# 4-PT100.net
KiCad netlist of a schematic drawn in EAGLE
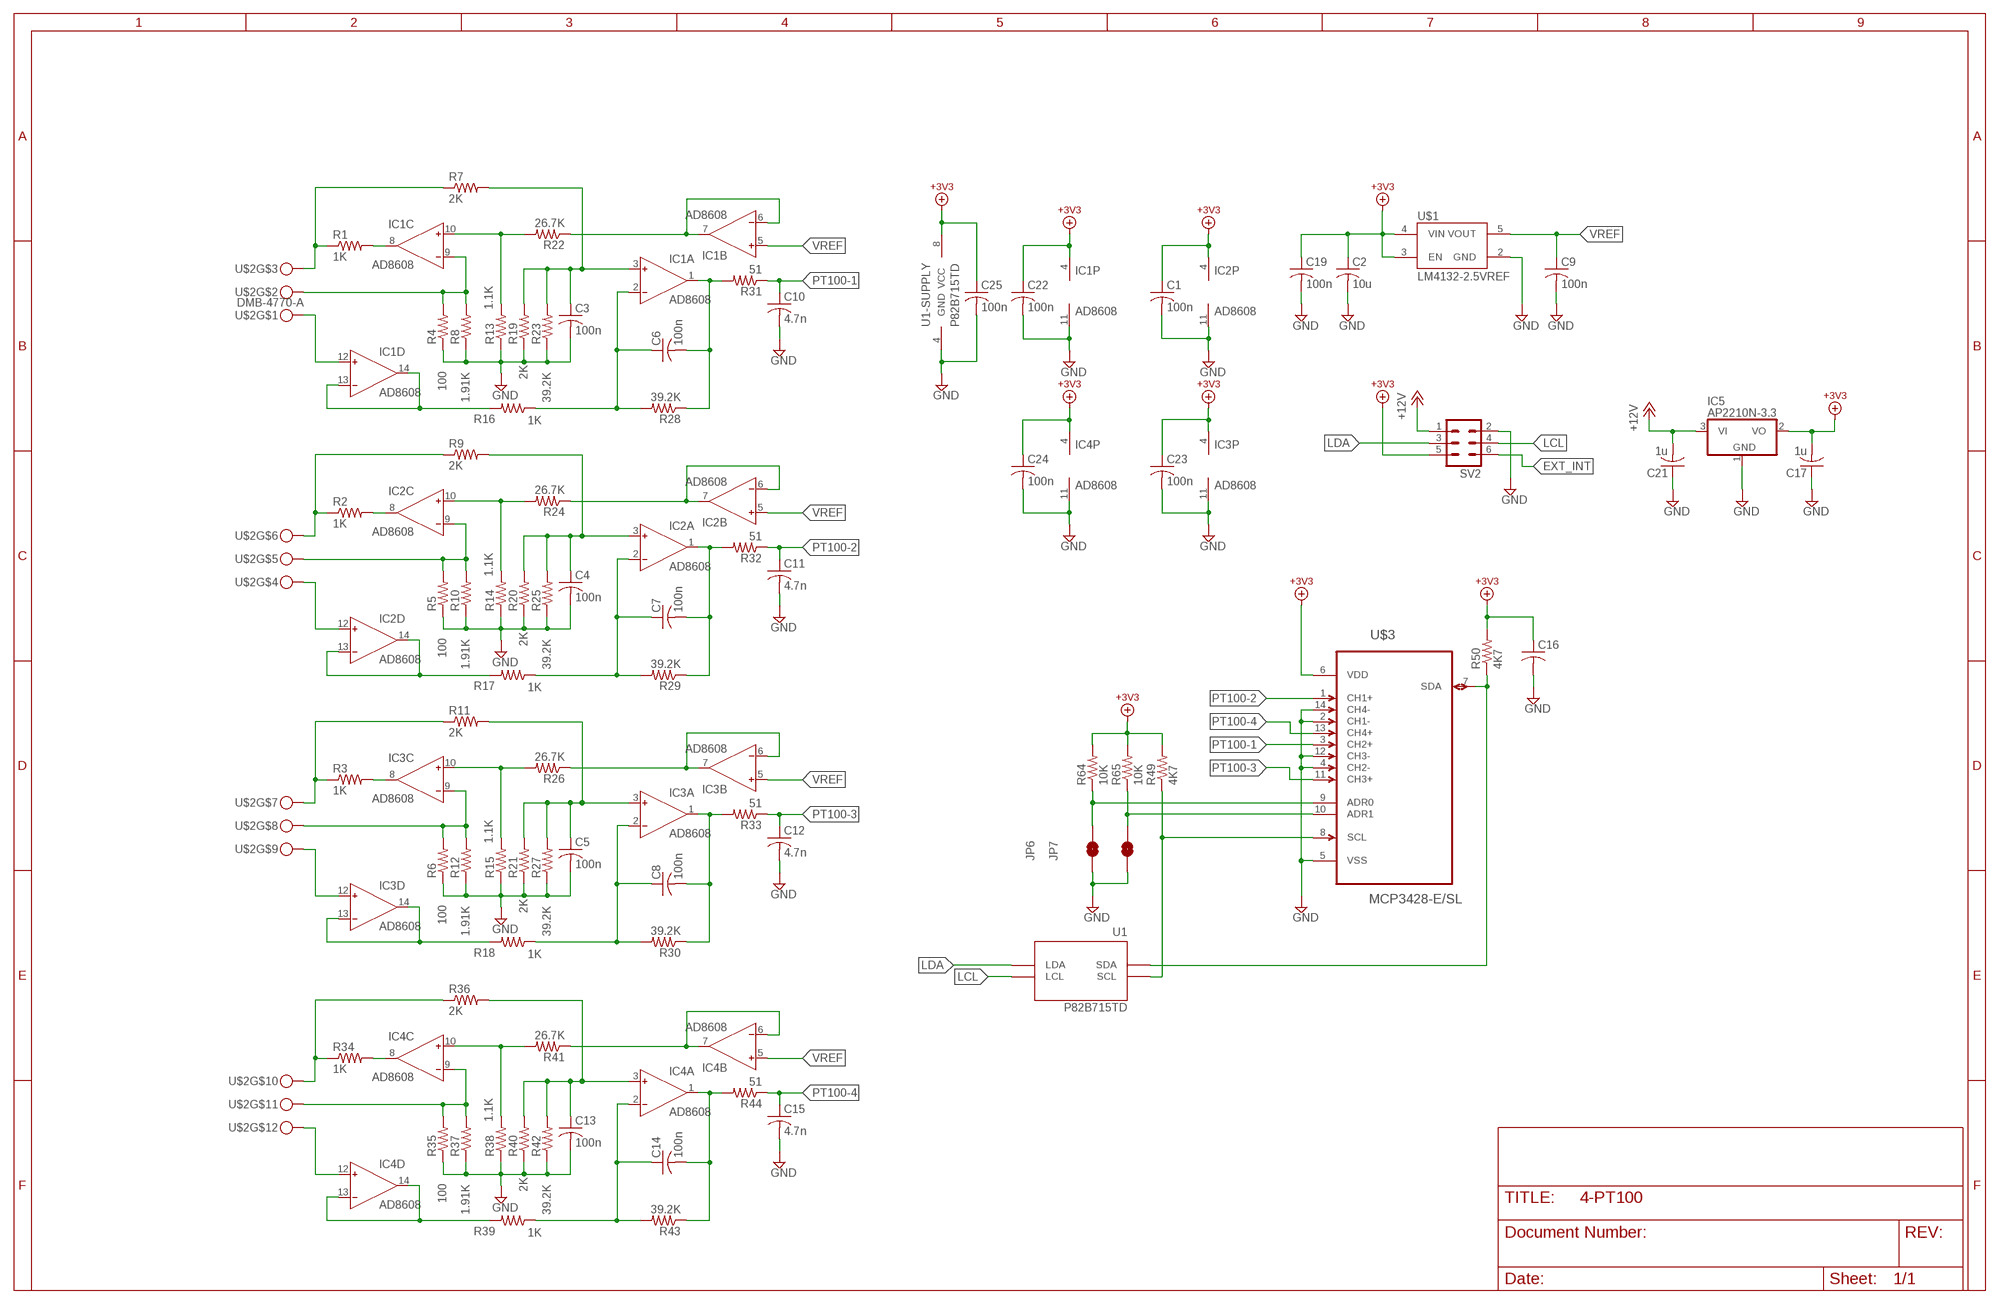
[diagram p0: schematic, sheet 1]

(export (version "E")
  (design (tool "Eeschema 10.0.6"))
  (components
    (comp (ref "C1")
      (value "100n")
      (footprint "eagle-import:C0805")
      (libsource (lib "eagle-import") (part "C-USC0805"))
    )
    (comp (ref "C2")
      (value "10u")
      (footprint "eagle-import:C0805")
      (libsource (lib "eagle-import") (part "C-USC0805"))
    )
    (comp (ref "C3")
      (value "100n")
      (footprint "eagle-import:C0805")
      (libsource (lib "eagle-import") (part "C-USC0805"))
    )
    (comp (ref "C4")
      (value "100n")
      (footprint "eagle-import:C0805")
      (libsource (lib "eagle-import") (part "C-USC0805"))
    )
    (comp (ref "C5")
      (value "100n")
      (footprint "eagle-import:C0805")
      (libsource (lib "eagle-import") (part "C-USC0805"))
    )
    (comp (ref "C6")
      (value "100n")
      (footprint "eagle-import:C0805")
      (libsource (lib "eagle-import") (part "C-USC0805"))
    )
    (comp (ref "C7")
      (value "100n")
      (footprint "eagle-import:C0805")
      (libsource (lib "eagle-import") (part "C-USC0805"))
    )
    (comp (ref "C8")
      (value "100n")
      (footprint "eagle-import:C0805")
      (libsource (lib "eagle-import") (part "C-USC0805"))
    )
    (comp (ref "C9")
      (value "100n")
      (footprint "eagle-import:C0805")
      (libsource (lib "eagle-import") (part "C-USC0805"))
    )
    (comp (ref "C10")
      (value "4.7n")
      (footprint "eagle-import:C0805")
      (libsource (lib "eagle-import") (part "C-USC0805"))
    )
    (comp (ref "C11")
      (value "4.7n")
      (footprint "eagle-import:C0805")
      (libsource (lib "eagle-import") (part "C-USC0805"))
    )
    (comp (ref "C12")
      (value "4.7n")
      (footprint "eagle-import:C0805")
      (libsource (lib "eagle-import") (part "C-USC0805"))
    )
    (comp (ref "C13")
      (value "100n")
      (footprint "eagle-import:C0805")
      (libsource (lib "eagle-import") (part "C-USC0805"))
    )
    (comp (ref "C14")
      (value "100n")
      (footprint "eagle-import:C0805")
      (libsource (lib "eagle-import") (part "C-USC0805"))
    )
    (comp (ref "C15")
      (value "4.7n")
      (footprint "eagle-import:C0805")
      (libsource (lib "eagle-import") (part "C-USC0805"))
    )
    (comp (ref "C16")
      (value "C-USC0805")
      (footprint "eagle-import:C0805")
      (libsource (lib "eagle-import") (part "C-USC0805"))
    )
    (comp (ref "C17")
      (value "1u")
      (footprint "eagle-import:C0805")
      (libsource (lib "eagle-import") (part "C-USC0805"))
    )
    (comp (ref "C19")
      (value "100n")
      (footprint "eagle-import:C0805")
      (libsource (lib "eagle-import") (part "C-USC0805"))
    )
    (comp (ref "C21")
      (value "1u")
      (footprint "eagle-import:C0805")
      (libsource (lib "eagle-import") (part "C-USC0805"))
    )
    (comp (ref "C22")
      (value "100n")
      (footprint "eagle-import:C0805")
      (libsource (lib "eagle-import") (part "C-USC0805"))
    )
    (comp (ref "C23")
      (value "100n")
      (footprint "eagle-import:C0805")
      (libsource (lib "eagle-import") (part "C-USC0805"))
    )
    (comp (ref "C24")
      (value "100n")
      (footprint "eagle-import:C0805")
      (libsource (lib "eagle-import") (part "C-USC0805"))
    )
    (comp (ref "C25")
      (value "100n")
      (footprint "eagle-import:C0805")
      (libsource (lib "eagle-import") (part "C-USC0805"))
    )
    (comp (ref "IC1")
      (value "AD8608")
      (footprint "eagle-import:SO14")
      (fields (field (name "MPN") "AD8609ARZ"))
      (libsource (lib "eagle-import") (part "AD8609R"))
    )
    (comp (ref "IC2")
      (value "AD8608")
      (footprint "eagle-import:SO14")
      (fields (field (name "MPN") "AD8609ARZ"))
      (libsource (lib "eagle-import") (part "AD8609R"))
    )
    (comp (ref "IC3")
      (value "AD8608")
      (footprint "eagle-import:SO14")
      (fields (field (name "MPN") "AD8609ARZ"))
      (libsource (lib "eagle-import") (part "AD8609R"))
    )
    (comp (ref "IC4")
      (value "AD8608")
      (footprint "eagle-import:SO14")
      (fields (field (name "MPN") "AD8609ARZ"))
      (libsource (lib "eagle-import") (part "AD8609R"))
    )
    (comp (ref "IC5")
      (value "AP2210N-3.3")
      (footprint "eagle-import:SOT23")
      (libsource (lib "eagle-import") (part "MCP1703CB"))
    )
    (comp (ref "JP6")
      (value "JUMPER-PAD-2-NOYES_SILK")
      (footprint "eagle-import:PAD-JUMPER-2-NO_YES_SILK")
      (libsource (lib "eagle-import") (part "JUMPER-PAD-2-NOYES_SILK"))
    )
    (comp (ref "JP7")
      (value "JUMPER-PAD-2-NOYES_SILK")
      (footprint "eagle-import:PAD-JUMPER-2-NO_YES_SILK")
      (libsource (lib "eagle-import") (part "JUMPER-PAD-2-NOYES_SILK"))
    )
    (comp (ref "R1")
      (value "1K")
      (footprint "eagle-import:R0805")
      (libsource (lib "eagle-import") (part "R-US_R0805"))
    )
    (comp (ref "R2")
      (value "1K")
      (footprint "eagle-import:R0805")
      (libsource (lib "eagle-import") (part "R-US_R0805"))
    )
    (comp (ref "R3")
      (value "1K")
      (footprint "eagle-import:R0805")
      (libsource (lib "eagle-import") (part "R-US_R0805"))
    )
    (comp (ref "R4")
      (value "100")
      (footprint "eagle-import:R0805")
      (libsource (lib "eagle-import") (part "R-US_R0805"))
    )
    (comp (ref "R5")
      (value "100")
      (footprint "eagle-import:R0805")
      (libsource (lib "eagle-import") (part "R-US_R0805"))
    )
    (comp (ref "R6")
      (value "100")
      (footprint "eagle-import:R0805")
      (libsource (lib "eagle-import") (part "R-US_R0805"))
    )
    (comp (ref "R7")
      (value "2K")
      (footprint "eagle-import:R0805")
      (libsource (lib "eagle-import") (part "R-US_R0805"))
    )
    (comp (ref "R8")
      (value "1.91K")
      (footprint "eagle-import:R0805")
      (libsource (lib "eagle-import") (part "R-US_R0805"))
    )
    (comp (ref "R9")
      (value "2K")
      (footprint "eagle-import:R0805")
      (libsource (lib "eagle-import") (part "R-US_R0805"))
    )
    (comp (ref "R10")
      (value "1.91K")
      (footprint "eagle-import:R0805")
      (libsource (lib "eagle-import") (part "R-US_R0805"))
    )
    (comp (ref "R11")
      (value "2K")
      (footprint "eagle-import:R0805")
      (libsource (lib "eagle-import") (part "R-US_R0805"))
    )
    (comp (ref "R12")
      (value "1.91K")
      (footprint "eagle-import:R0805")
      (libsource (lib "eagle-import") (part "R-US_R0805"))
    )
    (comp (ref "R13")
      (value "1.1K")
      (footprint "eagle-import:R0805")
      (libsource (lib "eagle-import") (part "R-US_R0805"))
    )
    (comp (ref "R14")
      (value "1.1K")
      (footprint "eagle-import:R0805")
      (libsource (lib "eagle-import") (part "R-US_R0805"))
    )
    (comp (ref "R15")
      (value "1.1K")
      (footprint "eagle-import:R0805")
      (libsource (lib "eagle-import") (part "R-US_R0805"))
    )
    (comp (ref "R16")
      (value "1K")
      (footprint "eagle-import:R0805")
      (libsource (lib "eagle-import") (part "R-US_R0805"))
    )
    (comp (ref "R17")
      (value "1K")
      (footprint "eagle-import:R0805")
      (libsource (lib "eagle-import") (part "R-US_R0805"))
    )
    (comp (ref "R18")
      (value "1K")
      (footprint "eagle-import:R0805")
      (libsource (lib "eagle-import") (part "R-US_R0805"))
    )
    (comp (ref "R19")
      (value "2K")
      (footprint "eagle-import:R0805")
      (libsource (lib "eagle-import") (part "R-US_R0805"))
    )
    (comp (ref "R20")
      (value "2K")
      (footprint "eagle-import:R0805")
      (libsource (lib "eagle-import") (part "R-US_R0805"))
    )
    (comp (ref "R21")
      (value "2K")
      (footprint "eagle-import:R0805")
      (libsource (lib "eagle-import") (part "R-US_R0805"))
    )
    (comp (ref "R22")
      (value "26.7K")
      (footprint "eagle-import:R0805")
      (libsource (lib "eagle-import") (part "R-US_R0805"))
    )
    (comp (ref "R23")
      (value "39.2K")
      (footprint "eagle-import:R0805")
      (libsource (lib "eagle-import") (part "R-US_R0805"))
    )
    (comp (ref "R24")
      (value "26.7K")
      (footprint "eagle-import:R0805")
      (libsource (lib "eagle-import") (part "R-US_R0805"))
    )
    (comp (ref "R25")
      (value "39.2K")
      (footprint "eagle-import:R0805")
      (libsource (lib "eagle-import") (part "R-US_R0805"))
    )
    (comp (ref "R26")
      (value "26.7K")
      (footprint "eagle-import:R0805")
      (libsource (lib "eagle-import") (part "R-US_R0805"))
    )
    (comp (ref "R27")
      (value "39.2K")
      (footprint "eagle-import:R0805")
      (libsource (lib "eagle-import") (part "R-US_R0805"))
    )
    (comp (ref "R28")
      (value "39.2K")
      (footprint "eagle-import:R0805")
      (libsource (lib "eagle-import") (part "R-US_R0805"))
    )
    (comp (ref "R29")
      (value "39.2K")
      (footprint "eagle-import:R0805")
      (libsource (lib "eagle-import") (part "R-US_R0805"))
    )
    (comp (ref "R30")
      (value "39.2K")
      (footprint "eagle-import:R0805")
      (libsource (lib "eagle-import") (part "R-US_R0805"))
    )
    (comp (ref "R31")
      (value "51")
      (footprint "eagle-import:R0805")
      (libsource (lib "eagle-import") (part "R-US_R0805"))
    )
    (comp (ref "R32")
      (value "51")
      (footprint "eagle-import:R0805")
      (libsource (lib "eagle-import") (part "R-US_R0805"))
    )
    (comp (ref "R33")
      (value "51")
      (footprint "eagle-import:R0805")
      (libsource (lib "eagle-import") (part "R-US_R0805"))
    )
    (comp (ref "R34")
      (value "1K")
      (footprint "eagle-import:R0805")
      (libsource (lib "eagle-import") (part "R-US_R0805"))
    )
    (comp (ref "R35")
      (value "100")
      (footprint "eagle-import:R0805")
      (libsource (lib "eagle-import") (part "R-US_R0805"))
    )
    (comp (ref "R36")
      (value "2K")
      (footprint "eagle-import:R0805")
      (libsource (lib "eagle-import") (part "R-US_R0805"))
    )
    (comp (ref "R37")
      (value "1.91K")
      (footprint "eagle-import:R0805")
      (libsource (lib "eagle-import") (part "R-US_R0805"))
    )
    (comp (ref "R38")
      (value "1.1K")
      (footprint "eagle-import:R0805")
      (libsource (lib "eagle-import") (part "R-US_R0805"))
    )
    (comp (ref "R39")
      (value "1K")
      (footprint "eagle-import:R0805")
      (libsource (lib "eagle-import") (part "R-US_R0805"))
    )
    (comp (ref "R40")
      (value "2K")
      (footprint "eagle-import:R0805")
      (libsource (lib "eagle-import") (part "R-US_R0805"))
    )
    (comp (ref "R41")
      (value "26.7K")
      (footprint "eagle-import:R0805")
      (libsource (lib "eagle-import") (part "R-US_R0805"))
    )
    (comp (ref "R42")
      (value "39.2K")
      (footprint "eagle-import:R0805")
      (libsource (lib "eagle-import") (part "R-US_R0805"))
    )
    (comp (ref "R43")
      (value "39.2K")
      (footprint "eagle-import:R0805")
      (libsource (lib "eagle-import") (part "R-US_R0805"))
    )
    (comp (ref "R44")
      (value "51")
      (footprint "eagle-import:R0805")
      (libsource (lib "eagle-import") (part "R-US_R0805"))
    )
    (comp (ref "R49")
      (value "4K7")
      (footprint "eagle-import:R0805")
      (libsource (lib "eagle-import") (part "R-US_R0805"))
    )
    (comp (ref "R50")
      (value "4K7")
      (footprint "eagle-import:R0805")
      (libsource (lib "eagle-import") (part "R-US_R0805"))
    )
    (comp (ref "R64")
      (value "10K")
      (footprint "eagle-import:R0805")
      (libsource (lib "eagle-import") (part "R-US_R0805"))
    )
    (comp (ref "R65")
      (value "10K")
      (footprint "eagle-import:R0805")
      (libsource (lib "eagle-import") (part "R-US_R0805"))
    )
    (comp (ref "SV2")
      (value "ML6")
      (footprint "eagle-import:ML6")
      (libsource (lib "eagle-import") (part "ML6"))
    )
    (comp (ref "U$1")
      (value "LM4132-2.5VREF")
      (footprint "eagle-import:SOT23-5")
      (libsource (lib "eagle-import") (part "LM4128-2.5VREF"))
    )
    (comp (ref "U$2")
      (value "DMB-4770-A")
      (footprint "eagle-import:DMB-4770-A-PKG")
      (libsource (lib "eagle-import") (part "DMB-4770-A"))
    )
    (comp (ref "U$3")
      (value "MCP3428-E/SL")
      (footprint "eagle-import:SOIC127P600X175-14N")
      (libsource (lib "eagle-import") (part "MCP3428-E/SL"))
    )
    (comp (ref "U1")
      (value "P82B715TD")
      (footprint "eagle-import:SOIC-8")
      (fields (field (name "MANUFACTURER") "NXP Semiconductors") (field (name "PART_NUMBER") "P82B715TD,118"))
      (libsource (lib "eagle-import") (part "P82B715?TD"))
    )
  )
  (nets
    (net (code "1") (name "+12V") (class "Default")
      (node (ref "C21") (pin "2") (pinfunction "2_2") (pintype "passive"))
      (node (ref "IC5") (pin "3") (pinfunction "VI_3") (pintype "input"))
      (node (ref "SV2") (pin "1") (pinfunction "1_1") (pintype "passive"))
    )
    (net (code "2") (name "EXT_INT") (class "Default")
      (node (ref "SV2") (pin "6") (pinfunction "6_6") (pintype "passive"))
    )
    (net (code "3") (name "GND") (class "Default")
      (node (ref "C1") (pin "2") (pinfunction "2_2") (pintype "passive"))
      (node (ref "C10") (pin "2") (pinfunction "2_2") (pintype "passive"))
      (node (ref "C11") (pin "2") (pinfunction "2_2") (pintype "passive"))
      (node (ref "C12") (pin "2") (pinfunction "2_2") (pintype "passive"))
      (node (ref "C13") (pin "2") (pinfunction "2_2") (pintype "passive"))
      (node (ref "C15") (pin "2") (pinfunction "2_2") (pintype "passive"))
      (node (ref "C16") (pin "2") (pinfunction "2_2") (pintype "passive"))
      (node (ref "C17") (pin "1") (pinfunction "1_1") (pintype "passive"))
      (node (ref "C19") (pin "2") (pinfunction "2_2") (pintype "passive"))
      (node (ref "C2") (pin "2") (pinfunction "2_2") (pintype "passive"))
      (node (ref "C21") (pin "1") (pinfunction "1_1") (pintype "passive"))
      (node (ref "C22") (pin "2") (pinfunction "2_2") (pintype "passive"))
      (node (ref "C23") (pin "2") (pinfunction "2_2") (pintype "passive"))
      (node (ref "C24") (pin "2") (pinfunction "2_2") (pintype "passive"))
      (node (ref "C25") (pin "2") (pinfunction "2_2") (pintype "passive"))
      (node (ref "C3") (pin "2") (pinfunction "2_2") (pintype "passive"))
      (node (ref "C4") (pin "2") (pinfunction "2_2") (pintype "passive"))
      (node (ref "C5") (pin "2") (pinfunction "2_2") (pintype "passive"))
      (node (ref "C9") (pin "2") (pinfunction "2_2") (pintype "passive"))
      (node (ref "IC1") (pin "11") (pinfunction "V-_11") (pintype "power_in"))
      (node (ref "IC2") (pin "11") (pinfunction "V-_11") (pintype "power_in"))
      (node (ref "IC3") (pin "11") (pinfunction "V-_11") (pintype "power_in"))
      (node (ref "IC4") (pin "11") (pinfunction "V-_11") (pintype "power_in"))
      (node (ref "IC5") (pin "1") (pinfunction "GND_1") (pintype "passive"))
      (node (ref "JP6") (pin "1") (pinfunction "1_1") (pintype "passive"))
      (node (ref "JP7") (pin "1") (pinfunction "1_1") (pintype "passive"))
      (node (ref "R10") (pin "1") (pinfunction "1_1") (pintype "passive"))
      (node (ref "R12") (pin "1") (pinfunction "1_1") (pintype "passive"))
      (node (ref "R13") (pin "1") (pinfunction "1_1") (pintype "passive"))
      (node (ref "R14") (pin "1") (pinfunction "1_1") (pintype "passive"))
      (node (ref "R15") (pin "1") (pinfunction "1_1") (pintype "passive"))
      (node (ref "R19") (pin "1") (pinfunction "1_1") (pintype "passive"))
      (node (ref "R20") (pin "1") (pinfunction "1_1") (pintype "passive"))
      (node (ref "R21") (pin "1") (pinfunction "1_1") (pintype "passive"))
      (node (ref "R23") (pin "1") (pinfunction "1_1") (pintype "passive"))
      (node (ref "R25") (pin "1") (pinfunction "1_1") (pintype "passive"))
      (node (ref "R27") (pin "1") (pinfunction "1_1") (pintype "passive"))
      (node (ref "R35") (pin "1") (pinfunction "1_1") (pintype "passive"))
      (node (ref "R37") (pin "1") (pinfunction "1_1") (pintype "passive"))
      (node (ref "R38") (pin "1") (pinfunction "1_1") (pintype "passive"))
      (node (ref "R4") (pin "1") (pinfunction "1_1") (pintype "passive"))
      (node (ref "R40") (pin "1") (pinfunction "1_1") (pintype "passive"))
      (node (ref "R42") (pin "1") (pinfunction "1_1") (pintype "passive"))
      (node (ref "R5") (pin "1") (pinfunction "1_1") (pintype "passive"))
      (node (ref "R6") (pin "1") (pinfunction "1_1") (pintype "passive"))
      (node (ref "R8") (pin "1") (pinfunction "1_1") (pintype "passive"))
      (node (ref "SV2") (pin "2") (pinfunction "2_2") (pintype "passive"))
      (node (ref "U$1") (pin "2") (pinfunction "GND_2") (pintype "bidirectional"))
      (node (ref "U$3") (pin "12") (pinfunction "CH3-_12") (pintype "input"))
      (node (ref "U$3") (pin "14") (pinfunction "CH4-_14") (pintype "input"))
      (node (ref "U$3") (pin "2") (pinfunction "CH1-_2") (pintype "input"))
      (node (ref "U$3") (pin "4") (pinfunction "CH2-_4") (pintype "input"))
      (node (ref "U$3") (pin "5") (pinfunction "VSS_5") (pintype "power_in"))
      (node (ref "U1") (pin "4") (pinfunction "GND_4") (pintype "bidirectional"))
    )
    (net (code "4") (name "LCL") (class "Default")
      (node (ref "SV2") (pin "4") (pinfunction "4_4") (pintype "passive"))
      (node (ref "U1") (pin "2") (pinfunction "LCL_2") (pintype "bidirectional"))
    )
    (net (code "5") (name "LDA") (class "Default")
      (node (ref "SV2") (pin "3") (pinfunction "3_3") (pintype "passive"))
      (node (ref "U1") (pin "7") (pinfunction "LDA_7") (pintype "bidirectional"))
    )
    (net (code "6") (name "Net-(IC1A-IN+)") (class "Default")
      (node (ref "C3") (pin "1") (pinfunction "1_1") (pintype "passive"))
      (node (ref "IC1") (pin "3") (pinfunction "IN+_3") (pintype "input"))
      (node (ref "R19") (pin "2") (pinfunction "2_2") (pintype "passive"))
      (node (ref "R23") (pin "2") (pinfunction "2_2") (pintype "passive"))
      (node (ref "R7") (pin "2") (pinfunction "2_2") (pintype "passive"))
    )
    (net (code "7") (name "Net-(IC1A-IN-)") (class "Default")
      (node (ref "C6") (pin "1") (pinfunction "1_1") (pintype "passive"))
      (node (ref "IC1") (pin "2") (pinfunction "IN-_2") (pintype "input"))
      (node (ref "R16") (pin "1") (pinfunction "1_1") (pintype "passive"))
      (node (ref "R28") (pin "2") (pinfunction "2_2") (pintype "passive"))
    )
    (net (code "8") (name "Net-(IC1A-OUT)") (class "Default")
      (node (ref "C6") (pin "2") (pinfunction "2_2") (pintype "passive"))
      (node (ref "IC1") (pin "1") (pinfunction "OUT_1") (pintype "output"))
      (node (ref "R28") (pin "1") (pinfunction "1_1") (pintype "passive"))
      (node (ref "R31") (pin "2") (pinfunction "2_2") (pintype "passive"))
    )
    (net (code "9") (name "Net-(IC1B-IN-)") (class "Default")
      (node (ref "IC1") (pin "6") (pinfunction "IN-_6") (pintype "input"))
      (node (ref "IC1") (pin "7") (pinfunction "OUT_7") (pintype "output"))
      (node (ref "R22") (pin "1") (pinfunction "1_1") (pintype "passive"))
    )
    (net (code "10") (name "Net-(IC1C-IN+)") (class "Default")
      (node (ref "IC1") (pin "10") (pinfunction "IN+_10") (pintype "input"))
      (node (ref "R13") (pin "2") (pinfunction "2_2") (pintype "passive"))
      (node (ref "R22") (pin "2") (pinfunction "2_2") (pintype "passive"))
    )
    (net (code "11") (name "Net-(IC1C-IN-)") (class "Default")
      (node (ref "IC1") (pin "9") (pinfunction "IN-_9") (pintype "input"))
      (node (ref "R4") (pin "2") (pinfunction "2_2") (pintype "passive"))
      (node (ref "R8") (pin "2") (pinfunction "2_2") (pintype "passive"))
      (node (ref "U$2") (pin "P$2") (pinfunction "KL_P$2") (pintype "passive"))
    )
    (net (code "12") (name "Net-(IC1C-OUT)") (class "Default")
      (node (ref "IC1") (pin "8") (pinfunction "OUT_8") (pintype "output"))
      (node (ref "R1") (pin "2") (pinfunction "2_2") (pintype "passive"))
    )
    (net (code "13") (name "Net-(IC1D-IN+)") (class "Default")
      (node (ref "IC1") (pin "12") (pinfunction "IN+_12") (pintype "input"))
      (node (ref "U$2") (pin "P$1") (pinfunction "KL_P$1") (pintype "passive"))
    )
    (net (code "14") (name "Net-(IC1D-IN-)") (class "Default")
      (node (ref "IC1") (pin "13") (pinfunction "IN-_13") (pintype "input"))
      (node (ref "IC1") (pin "14") (pinfunction "OUT_14") (pintype "output"))
      (node (ref "R16") (pin "2") (pinfunction "2_2") (pintype "passive"))
    )
    (net (code "15") (name "Net-(IC2A-IN+)") (class "Default")
      (node (ref "C4") (pin "1") (pinfunction "1_1") (pintype "passive"))
      (node (ref "IC2") (pin "3") (pinfunction "IN+_3") (pintype "input"))
      (node (ref "R20") (pin "2") (pinfunction "2_2") (pintype "passive"))
      (node (ref "R25") (pin "2") (pinfunction "2_2") (pintype "passive"))
      (node (ref "R9") (pin "2") (pinfunction "2_2") (pintype "passive"))
    )
    (net (code "16") (name "Net-(IC2A-IN-)") (class "Default")
      (node (ref "C7") (pin "1") (pinfunction "1_1") (pintype "passive"))
      (node (ref "IC2") (pin "2") (pinfunction "IN-_2") (pintype "input"))
      (node (ref "R17") (pin "1") (pinfunction "1_1") (pintype "passive"))
      (node (ref "R29") (pin "2") (pinfunction "2_2") (pintype "passive"))
    )
    (net (code "17") (name "Net-(IC2A-OUT)") (class "Default")
      (node (ref "C7") (pin "2") (pinfunction "2_2") (pintype "passive"))
      (node (ref "IC2") (pin "1") (pinfunction "OUT_1") (pintype "output"))
      (node (ref "R29") (pin "1") (pinfunction "1_1") (pintype "passive"))
      (node (ref "R32") (pin "2") (pinfunction "2_2") (pintype "passive"))
    )
    (net (code "18") (name "Net-(IC2B-IN-)") (class "Default")
      (node (ref "IC2") (pin "6") (pinfunction "IN-_6") (pintype "input"))
      (node (ref "IC2") (pin "7") (pinfunction "OUT_7") (pintype "output"))
      (node (ref "R24") (pin "1") (pinfunction "1_1") (pintype "passive"))
    )
    (net (code "19") (name "Net-(IC2C-IN+)") (class "Default")
      (node (ref "IC2") (pin "10") (pinfunction "IN+_10") (pintype "input"))
      (node (ref "R14") (pin "2") (pinfunction "2_2") (pintype "passive"))
      (node (ref "R24") (pin "2") (pinfunction "2_2") (pintype "passive"))
    )
    (net (code "20") (name "Net-(IC2C-IN-)") (class "Default")
      (node (ref "IC2") (pin "9") (pinfunction "IN-_9") (pintype "input"))
      (node (ref "R10") (pin "2") (pinfunction "2_2") (pintype "passive"))
      (node (ref "R5") (pin "2") (pinfunction "2_2") (pintype "passive"))
      (node (ref "U$2") (pin "P$5") (pinfunction "KL_P$5") (pintype "passive"))
    )
    (net (code "21") (name "Net-(IC2C-OUT)") (class "Default")
      (node (ref "IC2") (pin "8") (pinfunction "OUT_8") (pintype "output"))
      (node (ref "R2") (pin "2") (pinfunction "2_2") (pintype "passive"))
    )
    (net (code "22") (name "Net-(IC2D-IN+)") (class "Default")
      (node (ref "IC2") (pin "12") (pinfunction "IN+_12") (pintype "input"))
      (node (ref "U$2") (pin "P$4") (pinfunction "KL_P$4") (pintype "passive"))
    )
    (net (code "23") (name "Net-(IC2D-IN-)") (class "Default")
      (node (ref "IC2") (pin "13") (pinfunction "IN-_13") (pintype "input"))
      (node (ref "IC2") (pin "14") (pinfunction "OUT_14") (pintype "output"))
      (node (ref "R17") (pin "2") (pinfunction "2_2") (pintype "passive"))
    )
    (net (code "24") (name "Net-(IC3A-IN+)") (class "Default")
      (node (ref "C5") (pin "1") (pinfunction "1_1") (pintype "passive"))
      (node (ref "IC3") (pin "3") (pinfunction "IN+_3") (pintype "input"))
      (node (ref "R11") (pin "2") (pinfunction "2_2") (pintype "passive"))
      (node (ref "R21") (pin "2") (pinfunction "2_2") (pintype "passive"))
      (node (ref "R27") (pin "2") (pinfunction "2_2") (pintype "passive"))
    )
    (net (code "25") (name "Net-(IC3A-IN-)") (class "Default")
      (node (ref "C8") (pin "1") (pinfunction "1_1") (pintype "passive"))
      (node (ref "IC3") (pin "2") (pinfunction "IN-_2") (pintype "input"))
      (node (ref "R18") (pin "1") (pinfunction "1_1") (pintype "passive"))
      (node (ref "R30") (pin "2") (pinfunction "2_2") (pintype "passive"))
    )
    (net (code "26") (name "Net-(IC3A-OUT)") (class "Default")
      (node (ref "C8") (pin "2") (pinfunction "2_2") (pintype "passive"))
      (node (ref "IC3") (pin "1") (pinfunction "OUT_1") (pintype "output"))
      (node (ref "R30") (pin "1") (pinfunction "1_1") (pintype "passive"))
      (node (ref "R33") (pin "2") (pinfunction "2_2") (pintype "passive"))
    )
    (net (code "27") (name "Net-(IC3B-IN-)") (class "Default")
      (node (ref "IC3") (pin "6") (pinfunction "IN-_6") (pintype "input"))
      (node (ref "IC3") (pin "7") (pinfunction "OUT_7") (pintype "output"))
      (node (ref "R26") (pin "1") (pinfunction "1_1") (pintype "passive"))
    )
    (net (code "28") (name "Net-(IC3C-IN+)") (class "Default")
      (node (ref "IC3") (pin "10") (pinfunction "IN+_10") (pintype "input"))
      (node (ref "R15") (pin "2") (pinfunction "2_2") (pintype "passive"))
      (node (ref "R26") (pin "2") (pinfunction "2_2") (pintype "passive"))
    )
    (net (code "29") (name "Net-(IC3C-IN-)") (class "Default")
      (node (ref "IC3") (pin "9") (pinfunction "IN-_9") (pintype "input"))
      (node (ref "R12") (pin "2") (pinfunction "2_2") (pintype "passive"))
      (node (ref "R6") (pin "2") (pinfunction "2_2") (pintype "passive"))
      (node (ref "U$2") (pin "P$8") (pinfunction "KL_P$8") (pintype "passive"))
    )
    (net (code "30") (name "Net-(IC3C-OUT)") (class "Default")
      (node (ref "IC3") (pin "8") (pinfunction "OUT_8") (pintype "output"))
      (node (ref "R3") (pin "2") (pinfunction "2_2") (pintype "passive"))
    )
    (net (code "31") (name "Net-(IC3D-IN+)") (class "Default")
      (node (ref "IC3") (pin "12") (pinfunction "IN+_12") (pintype "input"))
      (node (ref "U$2") (pin "P$9") (pinfunction "KL_P$9") (pintype "passive"))
    )
    (net (code "32") (name "Net-(IC3D-IN-)") (class "Default")
      (node (ref "IC3") (pin "13") (pinfunction "IN-_13") (pintype "input"))
      (node (ref "IC3") (pin "14") (pinfunction "OUT_14") (pintype "output"))
      (node (ref "R18") (pin "2") (pinfunction "2_2") (pintype "passive"))
    )
    (net (code "33") (name "Net-(IC4A-IN+)") (class "Default")
      (node (ref "C13") (pin "1") (pinfunction "1_1") (pintype "passive"))
      (node (ref "IC4") (pin "3") (pinfunction "IN+_3") (pintype "input"))
      (node (ref "R36") (pin "2") (pinfunction "2_2") (pintype "passive"))
      (node (ref "R40") (pin "2") (pinfunction "2_2") (pintype "passive"))
      (node (ref "R42") (pin "2") (pinfunction "2_2") (pintype "passive"))
    )
    (net (code "34") (name "Net-(IC4A-IN-)") (class "Default")
      (node (ref "C14") (pin "1") (pinfunction "1_1") (pintype "passive"))
      (node (ref "IC4") (pin "2") (pinfunction "IN-_2") (pintype "input"))
      (node (ref "R39") (pin "1") (pinfunction "1_1") (pintype "passive"))
      (node (ref "R43") (pin "2") (pinfunction "2_2") (pintype "passive"))
    )
    (net (code "35") (name "Net-(IC4A-OUT)") (class "Default")
      (node (ref "C14") (pin "2") (pinfunction "2_2") (pintype "passive"))
      (node (ref "IC4") (pin "1") (pinfunction "OUT_1") (pintype "output"))
      (node (ref "R43") (pin "1") (pinfunction "1_1") (pintype "passive"))
      (node (ref "R44") (pin "2") (pinfunction "2_2") (pintype "passive"))
    )
    (net (code "36") (name "Net-(IC4B-IN-)") (class "Default")
      (node (ref "IC4") (pin "6") (pinfunction "IN-_6") (pintype "input"))
      (node (ref "IC4") (pin "7") (pinfunction "OUT_7") (pintype "output"))
      (node (ref "R41") (pin "1") (pinfunction "1_1") (pintype "passive"))
    )
    (net (code "37") (name "Net-(IC4C-IN+)") (class "Default")
      (node (ref "IC4") (pin "10") (pinfunction "IN+_10") (pintype "input"))
      (node (ref "R38") (pin "2") (pinfunction "2_2") (pintype "passive"))
      (node (ref "R41") (pin "2") (pinfunction "2_2") (pintype "passive"))
    )
    (net (code "38") (name "Net-(IC4C-IN-)") (class "Default")
      (node (ref "IC4") (pin "9") (pinfunction "IN-_9") (pintype "input"))
      (node (ref "R35") (pin "2") (pinfunction "2_2") (pintype "passive"))
      (node (ref "R37") (pin "2") (pinfunction "2_2") (pintype "passive"))
      (node (ref "U$2") (pin "P$11") (pinfunction "KL_P$11") (pintype "passive"))
    )
    (net (code "39") (name "Net-(IC4C-OUT)") (class "Default")
      (node (ref "IC4") (pin "8") (pinfunction "OUT_8") (pintype "output"))
      (node (ref "R34") (pin "2") (pinfunction "2_2") (pintype "passive"))
    )
    (net (code "40") (name "Net-(IC4D-IN+)") (class "Default")
      (node (ref "IC4") (pin "12") (pinfunction "IN+_12") (pintype "input"))
      (node (ref "U$2") (pin "P$12") (pinfunction "KL_P$12") (pintype "passive"))
    )
    (net (code "41") (name "Net-(IC4D-IN-)") (class "Default")
      (node (ref "IC4") (pin "13") (pinfunction "IN-_13") (pintype "input"))
      (node (ref "IC4") (pin "14") (pinfunction "OUT_14") (pintype "output"))
      (node (ref "R39") (pin "2") (pinfunction "2_2") (pintype "passive"))
    )
    (net (code "42") (name "Net-(U$2B-KL)") (class "Default")
      (node (ref "R34") (pin "1") (pinfunction "1_1") (pintype "passive"))
      (node (ref "R36") (pin "1") (pinfunction "1_1") (pintype "passive"))
      (node (ref "U$2") (pin "P$10") (pinfunction "KL_P$10") (pintype "passive"))
    )
    (net (code "43") (name "Net-(U$2F-KL)") (class "Default")
      (node (ref "R1") (pin "1") (pinfunction "1_1") (pintype "passive"))
      (node (ref "R7") (pin "1") (pinfunction "1_1") (pintype "passive"))
      (node (ref "U$2") (pin "P$3") (pinfunction "KL_P$3") (pintype "passive"))
    )
    (net (code "44") (name "Net-(U$2I-KL)") (class "Default")
      (node (ref "R2") (pin "1") (pinfunction "1_1") (pintype "passive"))
      (node (ref "R9") (pin "1") (pinfunction "1_1") (pintype "passive"))
      (node (ref "U$2") (pin "P$6") (pinfunction "KL_P$6") (pintype "passive"))
    )
    (net (code "45") (name "Net-(U$2J-KL)") (class "Default")
      (node (ref "R11") (pin "1") (pinfunction "1_1") (pintype "passive"))
      (node (ref "R3") (pin "1") (pinfunction "1_1") (pintype "passive"))
      (node (ref "U$2") (pin "P$7") (pinfunction "KL_P$7") (pintype "passive"))
    )
    (net (code "46") (name "Net-(U$3-ADR0)") (class "Default")
      (node (ref "JP6") (pin "2") (pinfunction "2_2") (pintype "passive"))
      (node (ref "R64") (pin "1") (pinfunction "1_1") (pintype "passive"))
      (node (ref "U$3") (pin "9") (pinfunction "ADR0_9") (pintype "passive"))
    )
    (net (code "47") (name "Net-(U$3-ADR1)") (class "Default")
      (node (ref "JP7") (pin "2") (pinfunction "2_2") (pintype "passive"))
      (node (ref "R65") (pin "1") (pinfunction "1_1") (pintype "passive"))
      (node (ref "U$3") (pin "10") (pinfunction "ADR1_10") (pintype "passive"))
    )
    (net (code "48") (name "Net-(U$3-SCL)") (class "Default")
      (node (ref "R49") (pin "1") (pinfunction "1_1") (pintype "passive"))
      (node (ref "U$3") (pin "8") (pinfunction "SCL_8") (pintype "input"))
      (node (ref "U1") (pin "3") (pinfunction "SCL_3") (pintype "bidirectional"))
    )
    (net (code "49") (name "Net-(U$3-SDA)") (class "Default")
      (node (ref "R50") (pin "1") (pinfunction "1_1") (pintype "passive"))
      (node (ref "U$3") (pin "7") (pinfunction "SDA_7") (pintype "bidirectional"))
      (node (ref "U1") (pin "6") (pinfunction "SDA_6") (pintype "bidirectional"))
    )
    (net (code "50") (name "PT100-1") (class "Default")
      (node (ref "C10") (pin "1") (pinfunction "1_1") (pintype "passive"))
      (node (ref "R31") (pin "1") (pinfunction "1_1") (pintype "passive"))
      (node (ref "U$3") (pin "3") (pinfunction "CH2+_3") (pintype "input"))
    )
    (net (code "51") (name "PT100-2") (class "Default")
      (node (ref "C11") (pin "1") (pinfunction "1_1") (pintype "passive"))
      (node (ref "R32") (pin "1") (pinfunction "1_1") (pintype "passive"))
      (node (ref "U$3") (pin "1") (pinfunction "CH1+_1") (pintype "input"))
    )
    (net (code "52") (name "PT100-3") (class "Default")
      (node (ref "C12") (pin "1") (pinfunction "1_1") (pintype "passive"))
      (node (ref "R33") (pin "1") (pinfunction "1_1") (pintype "passive"))
      (node (ref "U$3") (pin "11") (pinfunction "CH3+_11") (pintype "input"))
    )
    (net (code "53") (name "PT100-4") (class "Default")
      (node (ref "C15") (pin "1") (pinfunction "1_1") (pintype "passive"))
      (node (ref "R44") (pin "1") (pinfunction "1_1") (pintype "passive"))
      (node (ref "U$3") (pin "13") (pinfunction "CH4+_13") (pintype "input"))
    )
    (net (code "54") (name "V+3V3") (class "Default")
      (node (ref "C1") (pin "1") (pinfunction "1_1") (pintype "passive"))
      (node (ref "C16") (pin "1") (pinfunction "1_1") (pintype "passive"))
      (node (ref "C17") (pin "2") (pinfunction "2_2") (pintype "passive"))
      (node (ref "C19") (pin "1") (pinfunction "1_1") (pintype "passive"))
      (node (ref "C2") (pin "1") (pinfunction "1_1") (pintype "passive"))
      (node (ref "C22") (pin "1") (pinfunction "1_1") (pintype "passive"))
      (node (ref "C23") (pin "1") (pinfunction "1_1") (pintype "passive"))
      (node (ref "C24") (pin "1") (pinfunction "1_1") (pintype "passive"))
      (node (ref "C25") (pin "1") (pinfunction "1_1") (pintype "passive"))
      (node (ref "IC1") (pin "4") (pinfunction "V+_4") (pintype "power_in"))
      (node (ref "IC2") (pin "4") (pinfunction "V+_4") (pintype "power_in"))
      (node (ref "IC3") (pin "4") (pinfunction "V+_4") (pintype "power_in"))
      (node (ref "IC4") (pin "4") (pinfunction "V+_4") (pintype "power_in"))
      (node (ref "IC5") (pin "2") (pinfunction "VO_2") (pintype "passive"))
      (node (ref "R49") (pin "2") (pinfunction "2_2") (pintype "passive"))
      (node (ref "R50") (pin "2") (pinfunction "2_2") (pintype "passive"))
      (node (ref "R64") (pin "2") (pinfunction "2_2") (pintype "passive"))
      (node (ref "R65") (pin "2") (pinfunction "2_2") (pintype "passive"))
      (node (ref "SV2") (pin "5") (pinfunction "5_5") (pintype "passive"))
      (node (ref "U$1") (pin "3") (pinfunction "EN_3") (pintype "bidirectional"))
      (node (ref "U$1") (pin "4") (pinfunction "VIN_4") (pintype "bidirectional"))
      (node (ref "U$3") (pin "6") (pinfunction "VDD_6") (pintype "power_in"))
      (node (ref "U1") (pin "8") (pinfunction "VCC_8") (pintype "bidirectional"))
    )
    (net (code "55") (name "VREF") (class "Default")
      (node (ref "C9") (pin "1") (pinfunction "1_1") (pintype "passive"))
      (node (ref "IC1") (pin "5") (pinfunction "IN+_5") (pintype "input"))
      (node (ref "IC2") (pin "5") (pinfunction "IN+_5") (pintype "input"))
      (node (ref "IC3") (pin "5") (pinfunction "IN+_5") (pintype "input"))
      (node (ref "IC4") (pin "5") (pinfunction "IN+_5") (pintype "input"))
      (node (ref "U$1") (pin "5") (pinfunction "VOUT_5") (pintype "bidirectional"))
    )
  )
)
